# tail.net
KiCad netlist of a schematic drawn in EAGLE
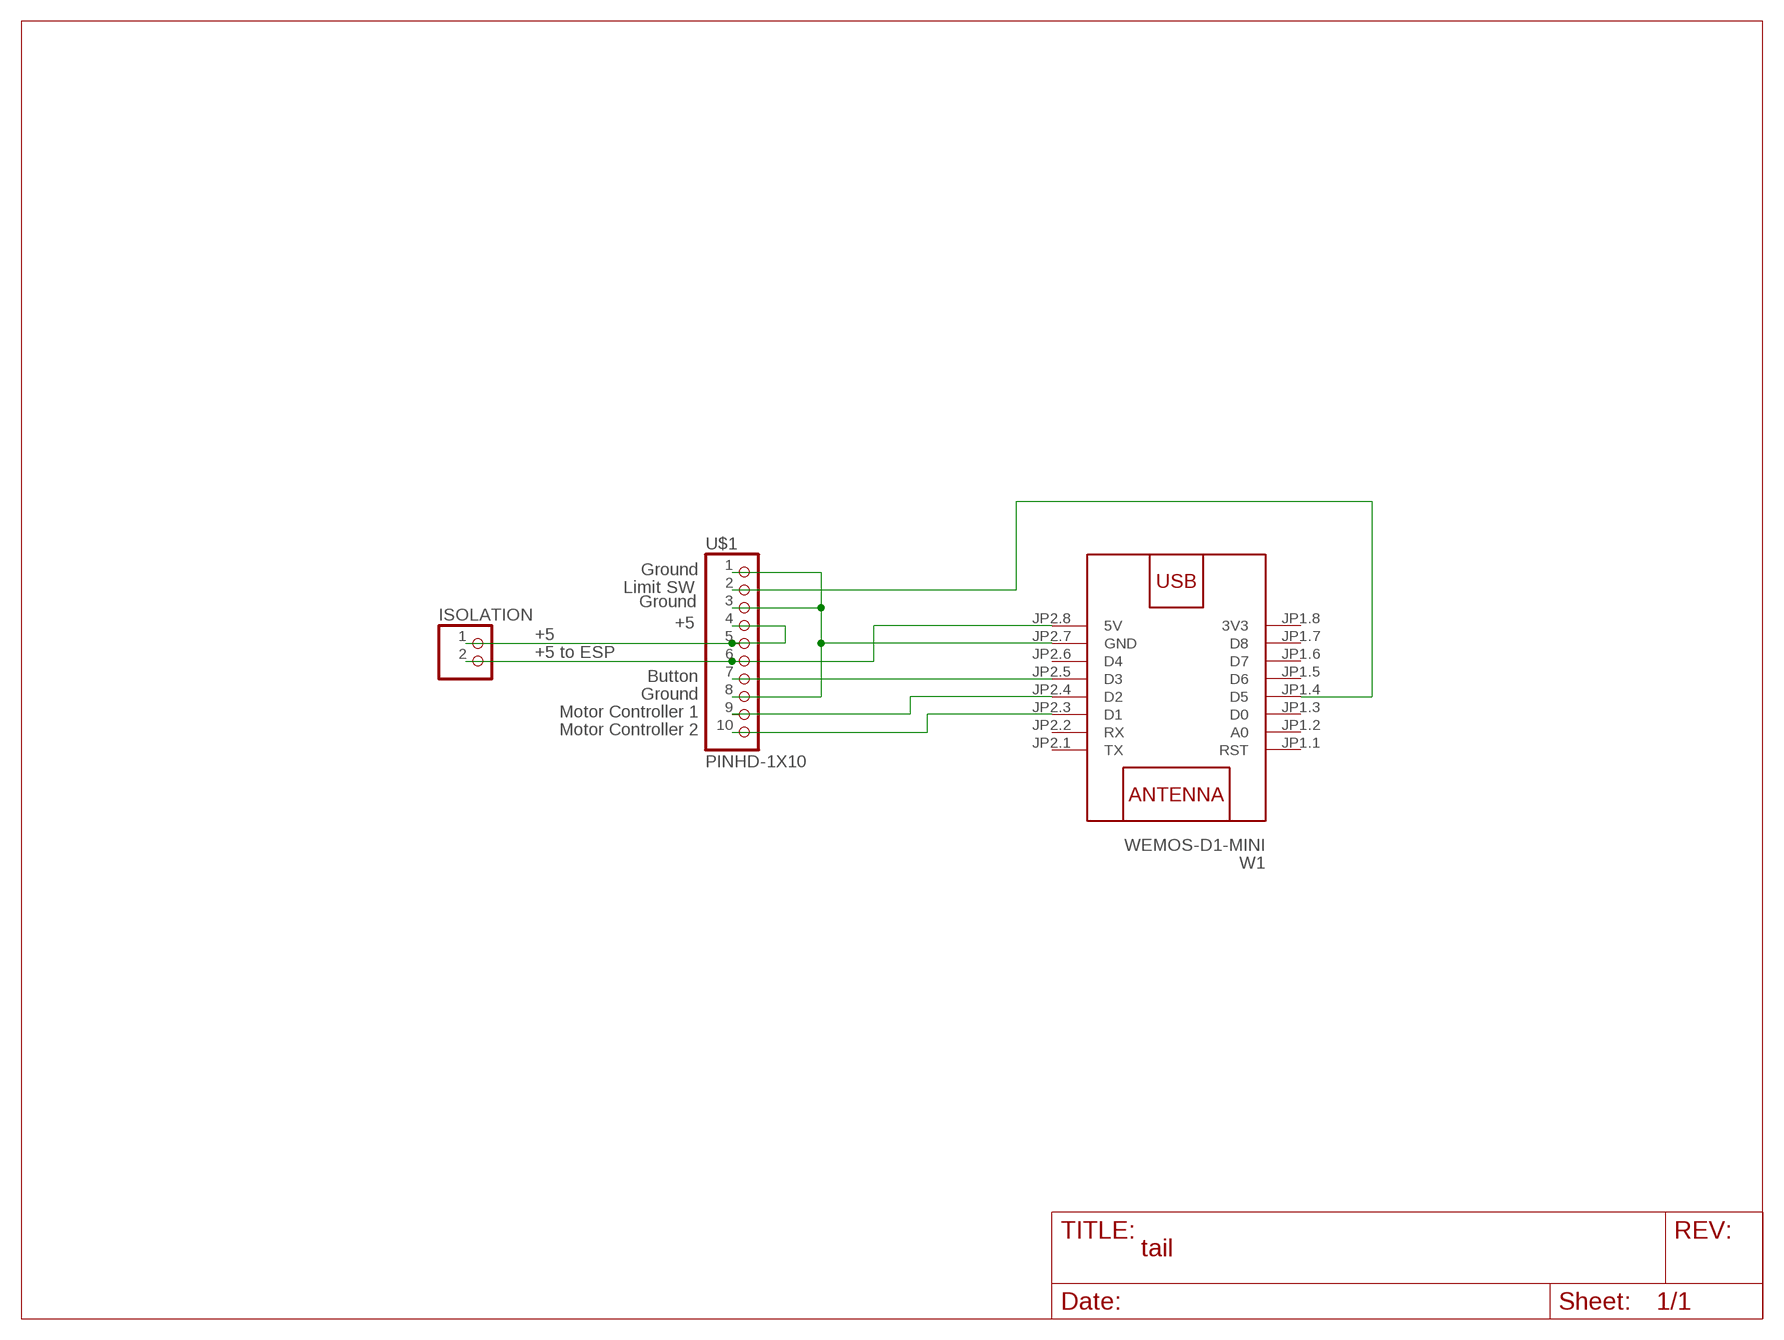
[diagram p0: schematic, sheet 1]

(export (version "E")
  (design (tool "Eeschema 10.0.6"))
  (components
    (comp (ref "ISOLATION")
      (value "PINHD-1X2")
      (footprint "eagle-import:1X02")
      (libsource (lib "eagle-import") (part "PINHD-1X2"))
    )
    (comp (ref "U$1")
      (value "PINHD-1X10")
      (footprint "eagle-import:1X10-BIG")
      (libsource (lib "eagle-import") (part "PINHD-1X10"))
    )
    (comp (ref "W1")
      (value "WEMOS-D1-MINI")
      (footprint "eagle-import:WEMOS-D1-MINI")
      (libsource (lib "eagle-import") (part "WEMOS-D1-MINI"))
    )
  )
  (nets
    (net (code "1") (name "/3V3") (class "Default")
      (node (ref "W1") (pin "JP1.8") (pinfunction "3V3_JP1.8") (pintype "power_in"))
    )
    (net (code "2") (name "Net-(ISOLATION-Pad1)") (class "Default")
      (node (ref "ISOLATION") (pin "1") (pinfunction "1_1") (pintype "passive"))
      (node (ref "U$1") (pin "4") (pinfunction "4_4") (pintype "passive"))
      (node (ref "U$1") (pin "5") (pinfunction "5_5") (pintype "passive"))
    )
    (net (code "3") (name "Net-(W1-5V)") (class "Default")
      (node (ref "ISOLATION") (pin "2") (pinfunction "2_2") (pintype "passive"))
      (node (ref "U$1") (pin "6") (pinfunction "6_6") (pintype "passive"))
      (node (ref "W1") (pin "JP2.8") (pinfunction "5V_JP2.8") (pintype "power_in"))
    )
    (net (code "4") (name "Net-(W1-D1)") (class "Default")
      (node (ref "U$1") (pin "10") (pinfunction "10_10") (pintype "passive"))
      (node (ref "W1") (pin "JP2.3") (pinfunction "D1_JP2.3") (pintype "bidirectional"))
    )
    (net (code "5") (name "Net-(W1-D2)") (class "Default")
      (node (ref "U$1") (pin "9") (pinfunction "9_9") (pintype "passive"))
      (node (ref "W1") (pin "JP2.4") (pinfunction "D2_JP2.4") (pintype "bidirectional"))
    )
    (net (code "6") (name "Net-(W1-D3)") (class "Default")
      (node (ref "U$1") (pin "7") (pinfunction "7_7") (pintype "passive"))
      (node (ref "W1") (pin "JP2.5") (pinfunction "D3_JP2.5") (pintype "bidirectional"))
    )
    (net (code "7") (name "Net-(W1-D5)") (class "Default")
      (node (ref "U$1") (pin "2") (pinfunction "2_2") (pintype "passive"))
      (node (ref "W1") (pin "JP1.4") (pinfunction "D5_JP1.4") (pintype "bidirectional"))
    )
    (net (code "8") (name "Net-(W1-GND)") (class "Default")
      (node (ref "U$1") (pin "1") (pinfunction "1_1") (pintype "passive"))
      (node (ref "U$1") (pin "3") (pinfunction "3_3") (pintype "passive"))
      (node (ref "U$1") (pin "8") (pinfunction "8_8") (pintype "passive"))
      (node (ref "W1") (pin "JP2.7") (pinfunction "GND_JP2.7") (pintype "power_in"))
    )
    (net (code "9") (name "unconnected-(W1-A0-PadJP1.2)") (class "Default")
      (node (ref "W1") (pin "JP1.2") (pinfunction "A0_JP1.2") (pintype "bidirectional"))
    )
    (net (code "10") (name "unconnected-(W1-D0-PadJP1.3)") (class "Default")
      (node (ref "W1") (pin "JP1.3") (pinfunction "D0_JP1.3") (pintype "bidirectional"))
    )
    (net (code "11") (name "unconnected-(W1-D4-PadJP2.6)") (class "Default")
      (node (ref "W1") (pin "JP2.6") (pinfunction "D4_JP2.6") (pintype "bidirectional"))
    )
    (net (code "12") (name "unconnected-(W1-D6-PadJP1.5)") (class "Default")
      (node (ref "W1") (pin "JP1.5") (pinfunction "D6_JP1.5") (pintype "bidirectional"))
    )
    (net (code "13") (name "unconnected-(W1-D7-PadJP1.6)") (class "Default")
      (node (ref "W1") (pin "JP1.6") (pinfunction "D7_JP1.6") (pintype "bidirectional"))
    )
    (net (code "14") (name "unconnected-(W1-D8-PadJP1.7)") (class "Default")
      (node (ref "W1") (pin "JP1.7") (pinfunction "D8_JP1.7") (pintype "bidirectional"))
    )
    (net (code "15") (name "unconnected-(W1-RST-PadJP1.1)") (class "Default")
      (node (ref "W1") (pin "JP1.1") (pinfunction "RST_JP1.1") (pintype "bidirectional"))
    )
    (net (code "16") (name "unconnected-(W1-RX-PadJP2.2)") (class "Default")
      (node (ref "W1") (pin "JP2.2") (pinfunction "RX_JP2.2") (pintype "bidirectional"))
    )
    (net (code "17") (name "unconnected-(W1-TX-PadJP2.1)") (class "Default")
      (node (ref "W1") (pin "JP2.1") (pinfunction "TX_JP2.1") (pintype "bidirectional"))
    )
  )
)
